# BabyBotHarnessPCB.net
KiCad netlist of a schematic drawn in EAGLE
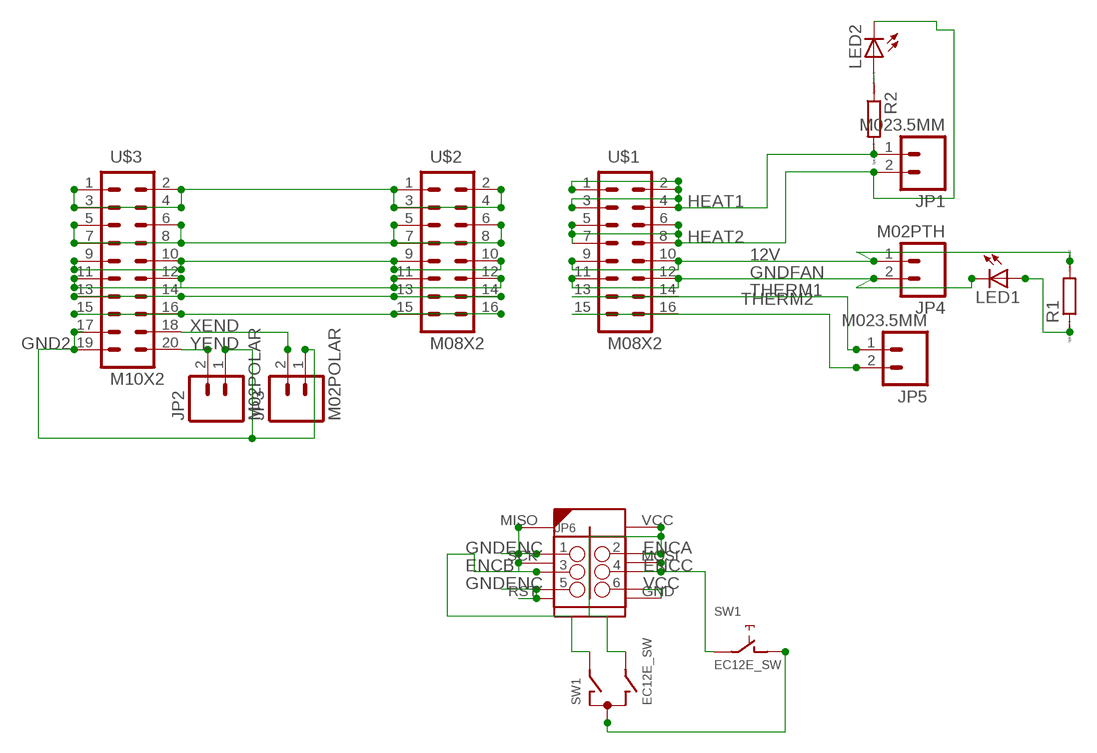
[diagram p0: schematic, sheet 1]

(export (version "E")
  (design (tool "Eeschema 10.0.6"))
  (components
    (comp (ref "JP1")
      (value "M023.5MM")
      (footprint "eagle-import:SCREWTERMINAL-3.5MM-2")
      (libsource (lib "eagle-import") (part "M023.5MM"))
    )
    (comp (ref "JP2")
      (value "M02POLAR")
      (footprint "eagle-import:MOLEX-1X2")
      (libsource (lib "eagle-import") (part "M02POLAR"))
    )
    (comp (ref "JP3")
      (value "M02POLAR")
      (footprint "eagle-import:MOLEX-1X2")
      (libsource (lib "eagle-import") (part "M02POLAR"))
    )
    (comp (ref "JP4")
      (value "M02PTH")
      (footprint "eagle-import:1X02")
      (libsource (lib "eagle-import") (part "M02PTH"))
    )
    (comp (ref "JP5")
      (value "M023.5MM")
      (footprint "eagle-import:SCREWTERMINAL-3.5MM-2")
      (libsource (lib "eagle-import") (part "M023.5MM"))
    )
    (comp (ref "JP6")
      (value "M03X2SHROUD")
      (footprint "eagle-import:2X3-SHROUDED")
      (libsource (lib "eagle-import") (part "M03X2SHROUD"))
    )
    (comp (ref "LED1")
      (value "LED5MM")
      (footprint "eagle-import:LED5MM")
      (libsource (lib "eagle-import") (part "LED5MM"))
    )
    (comp (ref "LED2")
      (value "LEDCHIPLED_1206")
      (footprint "eagle-import:CHIPLED_1206")
      (libsource (lib "eagle-import") (part "LEDCHIPLED_1206"))
    )
    (comp (ref "R1")
      (value "RR1206")
      (footprint "eagle-import:R1206")
      (libsource (lib "eagle-import") (part "RR1206"))
    )
    (comp (ref "R2")
      (value "RR1206")
      (footprint "eagle-import:R1206")
      (libsource (lib "eagle-import") (part "RR1206"))
    )
    (comp (ref "SW1")
      (value "EC12E_SW")
      (footprint "eagle-import:ALPS_EC12E_SW")
      (fields (field (name "MPN") "EC12E2424407"))
      (libsource (lib "eagle-import") (part "EC12E_SW"))
    )
    (comp (ref "U$1")
      (value "M08X2")
      (footprint "eagle-import:2X8")
      (libsource (lib "eagle-import") (part "M08X2"))
    )
    (comp (ref "U$2")
      (value "M08X2")
      (footprint "eagle-import:2X8")
      (libsource (lib "eagle-import") (part "M08X2"))
    )
    (comp (ref "U$3")
      (value "M10X2")
      (footprint "eagle-import:2X10")
      (libsource (lib "eagle-import") (part "M10X2"))
    )
    (comp (ref "U$4")
      (value "AVR-ISP-6-EDGE")
      (footprint "eagle-import:6PAD_ISP")
      (libsource (lib "eagle-import") (part "AVR-ISP-6-EDGE"))
    )
  )
  (nets
    (net (code "1") (name "/12V") (class "Default")
      (node (ref "JP4") (pin "1") (pinfunction "1_1") (pintype "passive"))
      (node (ref "R1") (pin "2") (pinfunction "2_2") (pintype "passive"))
      (node (ref "U$1") (pin "10") (pinfunction "10_10") (pintype "passive"))
      (node (ref "U$1") (pin "9") (pinfunction "9_9") (pintype "passive"))
    )
    (net (code "2") (name "/ENCA") (class "Default")
      (node (ref "JP6") (pin "2") (pinfunction "2_2") (pintype "bidirectional"))
      (node (ref "SW1") (pin "B") (pinfunction "B_B") (pintype "passive"))
      (node (ref "U$4") (pin "VCC") (pinfunction "P$6_VCC") (pintype "bidirectional"))
    )
    (net (code "3") (name "/ENCB") (class "Default")
      (node (ref "JP6") (pin "3") (pinfunction "3_3") (pintype "bidirectional"))
      (node (ref "SW1") (pin "A") (pinfunction "A_A") (pintype "passive"))
      (node (ref "U$4") (pin "SCK") (pinfunction "P$2_SCK") (pintype "bidirectional"))
    )
    (net (code "4") (name "/ENCC") (class "Default")
      (node (ref "JP6") (pin "4") (pinfunction "4_4") (pintype "bidirectional"))
      (node (ref "SW1") (pin "E") (pinfunction "2_E") (pintype "passive"))
      (node (ref "U$4") (pin "MOSI") (pinfunction "P$5_MOSI") (pintype "bidirectional"))
    )
    (net (code "5") (name "/GND2") (class "Default")
      (node (ref "JP2") (pin "1") (pinfunction "1_1") (pintype "passive"))
      (node (ref "JP3") (pin "1") (pinfunction "1_1") (pintype "passive"))
      (node (ref "U$3") (pin "17") (pinfunction "17_17") (pintype "passive"))
      (node (ref "U$3") (pin "19") (pinfunction "19_19") (pintype "passive"))
    )
    (net (code "6") (name "/GNDENC") (class "Default")
      (node (ref "JP6") (pin "1") (pinfunction "1_1") (pintype "bidirectional"))
      (node (ref "JP6") (pin "5") (pinfunction "5_5") (pintype "bidirectional"))
      (node (ref "SW1") (pin "C") (pinfunction "C_C") (pintype "passive"))
      (node (ref "SW1") (pin "D") (pinfunction "1_D") (pintype "passive"))
      (node (ref "U$4") (pin "MISO") (pinfunction "P$1_MISO") (pintype "bidirectional"))
      (node (ref "U$4") (pin "RST") (pinfunction "P$3_RST") (pintype "bidirectional"))
    )
    (net (code "7") (name "/GNDFAN") (class "Default")
      (node (ref "JP4") (pin "2") (pinfunction "2_2") (pintype "passive"))
      (node (ref "LED1") (pin "K") (pinfunction "C_K") (pintype "passive"))
      (node (ref "U$1") (pin "11") (pinfunction "11_11") (pintype "passive"))
      (node (ref "U$1") (pin "12") (pinfunction "12_12") (pintype "passive"))
    )
    (net (code "8") (name "/HEAT1") (class "Default")
      (node (ref "JP1") (pin "1") (pinfunction "1_1") (pintype "passive"))
      (node (ref "R2") (pin "2") (pinfunction "2_2") (pintype "passive"))
      (node (ref "U$1") (pin "1") (pinfunction "1_1") (pintype "passive"))
      (node (ref "U$1") (pin "2") (pinfunction "2_2") (pintype "passive"))
      (node (ref "U$1") (pin "3") (pinfunction "3_3") (pintype "passive"))
      (node (ref "U$1") (pin "4") (pinfunction "4_4") (pintype "passive"))
    )
    (net (code "9") (name "/HEAT2") (class "Default")
      (node (ref "JP1") (pin "2") (pinfunction "2_2") (pintype "passive"))
      (node (ref "LED2") (pin "C") (pinfunction "C_C") (pintype "passive"))
      (node (ref "U$1") (pin "5") (pinfunction "5_5") (pintype "passive"))
      (node (ref "U$1") (pin "6") (pinfunction "6_6") (pintype "passive"))
      (node (ref "U$1") (pin "7") (pinfunction "7_7") (pintype "passive"))
      (node (ref "U$1") (pin "8") (pinfunction "8_8") (pintype "passive"))
    )
    (net (code "10") (name "/THERM1") (class "Default")
      (node (ref "JP5") (pin "1") (pinfunction "1_1") (pintype "passive"))
      (node (ref "U$1") (pin "13") (pinfunction "13_13") (pintype "passive"))
      (node (ref "U$1") (pin "14") (pinfunction "14_14") (pintype "passive"))
    )
    (net (code "11") (name "/THERM2") (class "Default")
      (node (ref "JP5") (pin "2") (pinfunction "2_2") (pintype "passive"))
      (node (ref "U$1") (pin "15") (pinfunction "15_15") (pintype "passive"))
      (node (ref "U$1") (pin "16") (pinfunction "16_16") (pintype "passive"))
    )
    (net (code "12") (name "/VCC") (class "Default")
      (node (ref "JP6") (pin "6") (pinfunction "6_6") (pintype "bidirectional"))
      (node (ref "U$4") (pin "GND") (pinfunction "P$4_GND") (pintype "bidirectional"))
    )
    (net (code "13") (name "/XEND") (class "Default")
      (node (ref "JP3") (pin "2") (pinfunction "2_2") (pintype "passive"))
      (node (ref "U$3") (pin "18") (pinfunction "18_18") (pintype "passive"))
    )
    (net (code "14") (name "/YEND") (class "Default")
      (node (ref "JP2") (pin "2") (pinfunction "2_2") (pintype "passive"))
      (node (ref "U$3") (pin "20") (pinfunction "20_20") (pintype "passive"))
    )
    (net (code "15") (name "Net-(LED1-PadA)") (class "Default")
      (node (ref "LED1") (pin "A") (pinfunction "A_A") (pintype "passive"))
      (node (ref "R1") (pin "1") (pinfunction "1_1") (pintype "passive"))
    )
    (net (code "16") (name "Net-(LED2-PadA)") (class "Default")
      (node (ref "LED2") (pin "A") (pinfunction "A_A") (pintype "passive"))
      (node (ref "R2") (pin "1") (pinfunction "1_1") (pintype "passive"))
    )
    (net (code "17") (name "Net-(U$2-Pad1)") (class "Default")
      (node (ref "U$2") (pin "1") (pinfunction "1_1") (pintype "passive"))
      (node (ref "U$2") (pin "2") (pinfunction "2_2") (pintype "passive"))
      (node (ref "U$2") (pin "3") (pinfunction "3_3") (pintype "passive"))
      (node (ref "U$2") (pin "4") (pinfunction "4_4") (pintype "passive"))
      (node (ref "U$3") (pin "1") (pinfunction "1_1") (pintype "passive"))
      (node (ref "U$3") (pin "2") (pinfunction "2_2") (pintype "passive"))
      (node (ref "U$3") (pin "3") (pinfunction "3_3") (pintype "passive"))
      (node (ref "U$3") (pin "4") (pinfunction "4_4") (pintype "passive"))
    )
    (net (code "18") (name "Net-(U$2-Pad5)") (class "Default")
      (node (ref "U$2") (pin "5") (pinfunction "5_5") (pintype "passive"))
      (node (ref "U$2") (pin "6") (pinfunction "6_6") (pintype "passive"))
      (node (ref "U$2") (pin "7") (pinfunction "7_7") (pintype "passive"))
      (node (ref "U$2") (pin "8") (pinfunction "8_8") (pintype "passive"))
      (node (ref "U$3") (pin "5") (pinfunction "5_5") (pintype "passive"))
      (node (ref "U$3") (pin "6") (pinfunction "6_6") (pintype "passive"))
      (node (ref "U$3") (pin "7") (pinfunction "7_7") (pintype "passive"))
      (node (ref "U$3") (pin "8") (pinfunction "8_8") (pintype "passive"))
    )
    (net (code "19") (name "Net-(U$2-Pad10)") (class "Default")
      (node (ref "U$2") (pin "10") (pinfunction "10_10") (pintype "passive"))
      (node (ref "U$2") (pin "9") (pinfunction "9_9") (pintype "passive"))
      (node (ref "U$3") (pin "10") (pinfunction "10_10") (pintype "passive"))
      (node (ref "U$3") (pin "9") (pinfunction "9_9") (pintype "passive"))
    )
    (net (code "20") (name "Net-(U$2-Pad11)") (class "Default")
      (node (ref "U$2") (pin "11") (pinfunction "11_11") (pintype "passive"))
      (node (ref "U$2") (pin "12") (pinfunction "12_12") (pintype "passive"))
      (node (ref "U$3") (pin "11") (pinfunction "11_11") (pintype "passive"))
      (node (ref "U$3") (pin "12") (pinfunction "12_12") (pintype "passive"))
    )
    (net (code "21") (name "Net-(U$2-Pad13)") (class "Default")
      (node (ref "U$2") (pin "13") (pinfunction "13_13") (pintype "passive"))
      (node (ref "U$2") (pin "14") (pinfunction "14_14") (pintype "passive"))
      (node (ref "U$3") (pin "13") (pinfunction "13_13") (pintype "passive"))
      (node (ref "U$3") (pin "14") (pinfunction "14_14") (pintype "passive"))
    )
    (net (code "22") (name "Net-(U$2-Pad15)") (class "Default")
      (node (ref "U$2") (pin "15") (pinfunction "15_15") (pintype "passive"))
      (node (ref "U$2") (pin "16") (pinfunction "16_16") (pintype "passive"))
      (node (ref "U$3") (pin "15") (pinfunction "15_15") (pintype "passive"))
      (node (ref "U$3") (pin "16") (pinfunction "16_16") (pintype "passive"))
    )
  )
)
